# 01_powersupply.net
KiCad netlist of a schematic drawn in Altium Designer
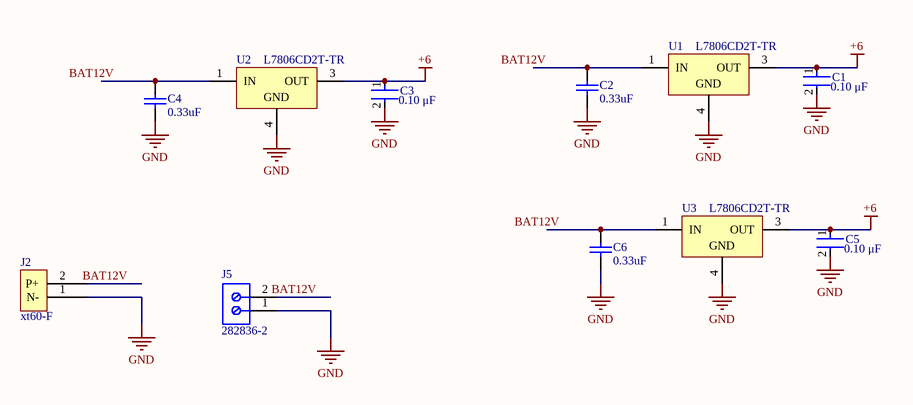
[diagram p0: 01_powersupply.SchDoc]

(export (version "E")
  (design (tool "Eeschema 10.0.6"))
  (components
    (comp (ref "C1")
      (value "C0603C104M4RAC7411")
      (footprint "FP-C0603C-CF-MFG")
      (description "CAP CER 0.1UF 16V X7R 0603")
      (fields
        (field (name "TOLERANCE") "0.2")
        (field (name "CAPACITANCE") "0.10 μF")
        (field (name "MANUFACTURER") "KEMET")
      )
      (libsource (lib "Altium Content Vault") (part "b4654b650e69147ec39a6b967a45e02"))
    )
    (comp (ref "C2")
      (value "0.33uF")
      (footprint "CAPC1608X90X20LL10")
      (description "Chip Capacitor, 0.33 uF, +/- 10%, 50 V, -55 to 125 degC, 0603 (1608 Metric), RoHS, Tape and Reel")
      (fields (field (name "MANUFACTURER") "TDK") (field (name "Comment") "C1608X7R1H334K080AC"))
      (libsource (lib "Altium Content Vault") (part "CAP-NP-2"))
    )
    (comp (ref "C3")
      (value "C0603C104M4RAC7411")
      (footprint "FP-C0603C-CF-MFG")
      (description "CAP CER 0.1UF 16V X7R 0603")
      (fields
        (field (name "TOLERANCE") "0.2")
        (field (name "CAPACITANCE") "0.10 μF")
        (field (name "MANUFACTURER") "KEMET")
      )
      (libsource (lib "Altium Content Vault") (part "b4654b650e69147ec39a6b967a45e02"))
    )
    (comp (ref "C4")
      (value "0.33uF")
      (footprint "CAPC1608X90X20LL10")
      (description "Chip Capacitor, 0.33 uF, +/- 10%, 50 V, -55 to 125 degC, 0603 (1608 Metric), RoHS, Tape and Reel")
      (fields (field (name "MANUFACTURER") "TDK") (field (name "Comment") "C1608X7R1H334K080AC"))
      (libsource (lib "Altium Content Vault") (part "CAP-NP-2"))
    )
    (comp (ref "C5")
      (value "C0603C104M4RAC7411")
      (footprint "FP-C0603C-CF-MFG")
      (description "CAP CER 0.1UF 16V X7R 0603")
      (fields
        (field (name "TOLERANCE") "0.2")
        (field (name "CAPACITANCE") "0.10 μF")
        (field (name "MANUFACTURER") "KEMET")
      )
      (libsource (lib "Altium Content Vault") (part "b4654b650e69147ec39a6b967a45e02"))
    )
    (comp (ref "C6")
      (value "0.33uF")
      (footprint "CAPC1608X90X20LL10")
      (description "Chip Capacitor, 0.33 uF, +/- 10%, 50 V, -55 to 125 degC, 0603 (1608 Metric), RoHS, Tape and Reel")
      (fields (field (name "MANUFACTURER") "TDK") (field (name "Comment") "C1608X7R1H334K080AC"))
      (libsource (lib "Altium Content Vault") (part "CAP-NP-2"))
    )
    (comp (ref "J2") (value "xt60-F") (footprint "XT60H-F") (libsource (lib "Finger_module") (part "xt60")))
    (comp (ref "J5")
      (value "282836-2")
      (footprint "TECO-282836-2_V")
      (description "Female Header, Pitch 5 mm, 1 x 2 Position, Height 10 mm, Tail Length 3.5 mm, Rohs, Bulk")
      (fields (field (name "VOLTAGE") "300V") (field (name "MANUFACTURER") "TE Connectivity"))
      (libsource (lib "Altium Content Vault") (part "CN-1P-F-TB2"))
    )
    (comp (ref "U1")
      (value "L7806CD2T-TR")
      (footprint "TO-263_L")
      (description "Positive Voltage Regulator, 3-Pin D2PAK, Tape and Reel")
      (libsource (lib "Altium Content Vault") (part "PM-REG-L4940-SOT3"))
    )
    (comp (ref "U2")
      (value "L7806CD2T-TR")
      (footprint "TO-263_L")
      (description "Positive Voltage Regulator, 3-Pin D2PAK, Tape and Reel")
      (libsource (lib "Altium Content Vault") (part "PM-REG-L4940-SOT3"))
    )
    (comp (ref "U3")
      (value "L7806CD2T-TR")
      (footprint "TO-263_L")
      (description "Positive Voltage Regulator, 3-Pin D2PAK, Tape and Reel")
      (libsource (lib "Altium Content Vault") (part "PM-REG-L4940-SOT3"))
    )
  )
  (nets
    (net (code "1") (name "+6") (class "Default")
      (node (ref "C1") (pin "1") (pinfunction "1_1") (pintype "passive"))
      (node (ref "C3") (pin "1") (pinfunction "1_1") (pintype "passive"))
      (node (ref "C5") (pin "1") (pinfunction "1_1") (pintype "passive"))
      (node (ref "U1") (pin "3") (pinfunction "OUT_3") (pintype "power_in"))
      (node (ref "U2") (pin "3") (pinfunction "OUT_3") (pintype "power_in"))
      (node (ref "U3") (pin "3") (pinfunction "OUT_3") (pintype "power_in"))
    )
    (net (code "2") (name "/BAT12V") (class "Default")
      (node (ref "C2") (pin "2") (pinfunction "2_2") (pintype "passive"))
      (node (ref "C4") (pin "2") (pinfunction "2_2") (pintype "passive"))
      (node (ref "C6") (pin "2") (pinfunction "2_2") (pintype "passive"))
      (node (ref "J2") (pin "2") (pinfunction "P+_2") (pintype "power_in"))
      (node (ref "J5") (pin "2") (pinfunction "2_2") (pintype "passive"))
      (node (ref "U1") (pin "1") (pinfunction "IN_1") (pintype "power_in"))
      (node (ref "U2") (pin "1") (pinfunction "IN_1") (pintype "power_in"))
      (node (ref "U3") (pin "1") (pinfunction "IN_1") (pintype "power_in"))
    )
    (net (code "3") (name "GND") (class "Default")
      (node (ref "C1") (pin "2") (pinfunction "2_2") (pintype "passive"))
      (node (ref "C2") (pin "1") (pinfunction "1_1") (pintype "passive"))
      (node (ref "C3") (pin "2") (pinfunction "2_2") (pintype "passive"))
      (node (ref "C4") (pin "1") (pinfunction "1_1") (pintype "passive"))
      (node (ref "C5") (pin "2") (pinfunction "2_2") (pintype "passive"))
      (node (ref "C6") (pin "1") (pinfunction "1_1") (pintype "passive"))
      (node (ref "J2") (pin "1") (pinfunction "N-_1") (pintype "power_in"))
      (node (ref "J5") (pin "1") (pinfunction "1_1") (pintype "passive"))
      (node (ref "U1") (pin "4") (pinfunction "GND_4") (pintype "power_in"))
      (node (ref "U2") (pin "4") (pinfunction "GND_4") (pintype "power_in"))
      (node (ref "U3") (pin "4") (pinfunction "GND_4") (pintype "power_in"))
    )
  )
)
